# USBC-OVC_LIMIT.net
KiCad netlist of a schematic drawn in EAGLE
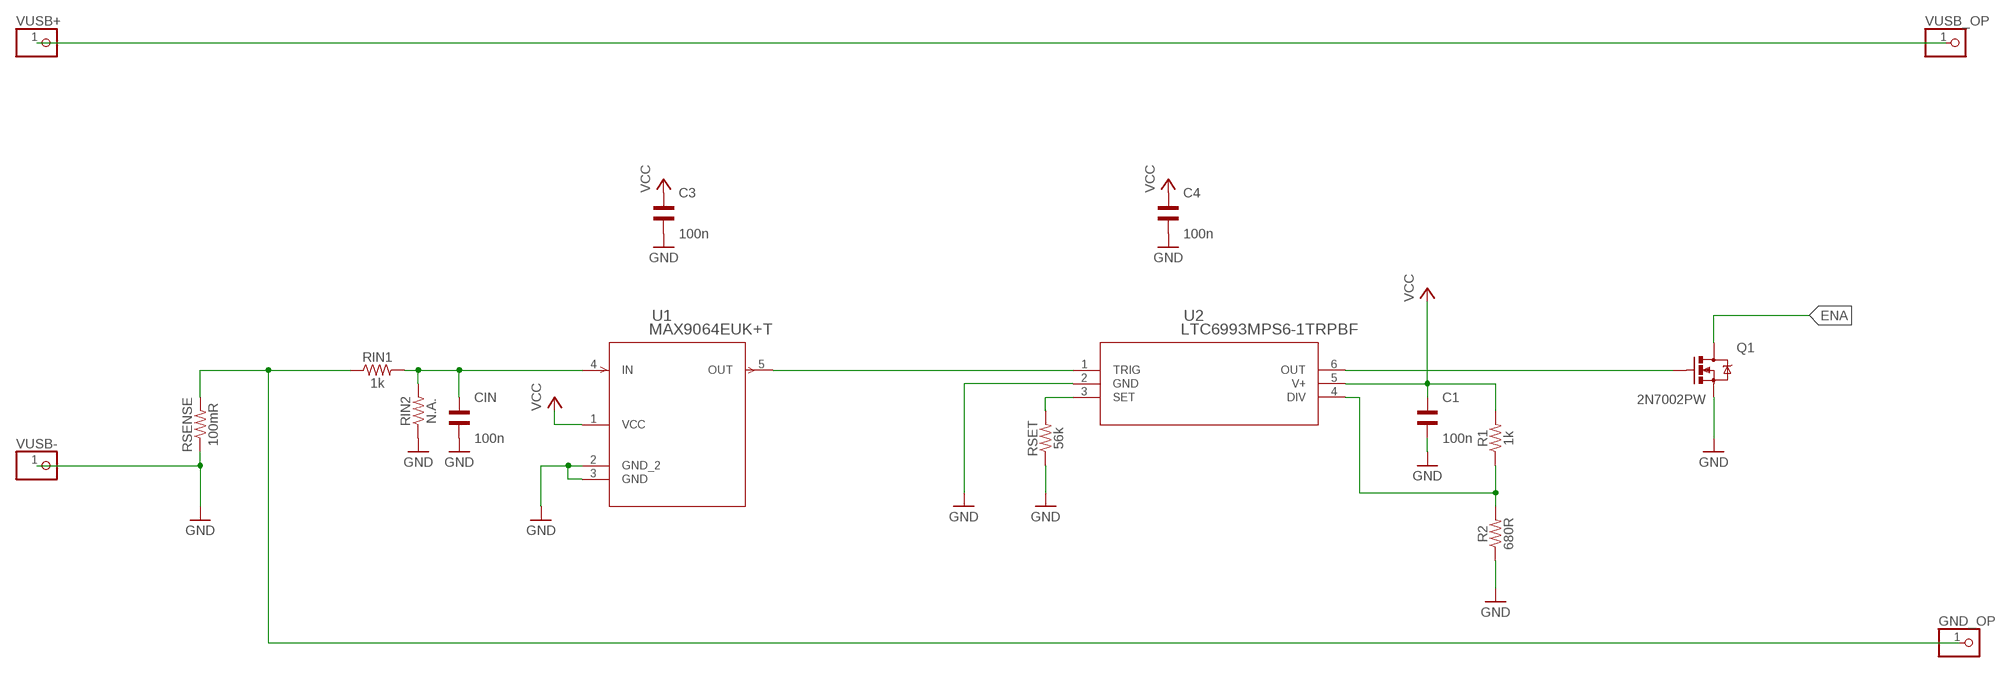
[diagram p0: schematic, sheet 1]

(export (version "E")
  (design (tool "Eeschema 10.0.6"))
  (components
    (comp (ref "C1")
      (value "100n")
      (footprint "eagle-import:WCAP-CSGP_1206")
      (libsource (lib "eagle-import") (part "WCAP-CSGP_1206_885012008001"))
    )
    (comp (ref "C3")
      (value "100n")
      (footprint "eagle-import:WCAP-CSGP_1206")
      (libsource (lib "eagle-import") (part "WCAP-CSGP_1206_885012008001"))
    )
    (comp (ref "C4")
      (value "100n")
      (footprint "eagle-import:WCAP-CSGP_1206")
      (libsource (lib "eagle-import") (part "WCAP-CSGP_1206_885012008001"))
    )
    (comp (ref "CIN")
      (value "100n")
      (footprint "eagle-import:WCAP-CSGP_1206")
      (libsource (lib "eagle-import") (part "WCAP-CSGP_1206_885012008001"))
    )
    (comp (ref "GND_OP")
      (value "PINHD-1X1")
      (footprint "eagle-import:1X01")
      (libsource (lib "eagle-import") (part "PINHD-1X1"))
    )
    (comp (ref "Q1")
      (value "2N7002PW")
      (footprint "eagle-import:SOT323")
      (libsource (lib "eagle-import") (part "MOSFET-NCHANNEL2N7002PW"))
    )
    (comp (ref "R1")
      (value "1k")
      (footprint "eagle-import:1206")
      (libsource (lib "eagle-import") (part "RESISTOR1206"))
    )
    (comp (ref "R2")
      (value "680R")
      (footprint "eagle-import:1206")
      (libsource (lib "eagle-import") (part "RESISTOR1206"))
    )
    (comp (ref "RIN1")
      (value "1k")
      (footprint "eagle-import:1206")
      (libsource (lib "eagle-import") (part "RESISTOR1206"))
    )
    (comp (ref "RIN2")
      (value "N.A.")
      (footprint "eagle-import:1206")
      (libsource (lib "eagle-import") (part "RESISTOR1206"))
    )
    (comp (ref "RSENSE")
      (value "100mR")
      (footprint "eagle-import:1206")
      (libsource (lib "eagle-import") (part "RESISTOR1206"))
    )
    (comp (ref "RSET")
      (value "56k")
      (footprint "eagle-import:1206")
      (libsource (lib "eagle-import") (part "RESISTOR1206"))
    )
    (comp (ref "U1")
      (value "MAX9064EUK+T")
      (footprint "eagle-import:21-0057F_MXM")
      (fields (field (name "COPYRIGHT") "Copyright (C) 2022 Ultra Librarian. All rights reserved."))
      (libsource (lib "eagle-import") (part "MAX9064EUK+T"))
    )
    (comp (ref "U2")
      (value "LTC6993MPS6-1TRPBF")
      (footprint "eagle-import:TSOT-23_S6_LIT")
      (fields
        (field (name "MANUFACTURER_PART_NUMBER") "LTC6993MPS6-1#TRPBF")
        (field (name "COPYRIGHT") "Copyright (C) 2022 Ultra Librarian. All rights reserved.")
      )
      (libsource (lib "eagle-import") (part "LTC6993MPS6-1TRPBF"))
    )
    (comp (ref "VUSB+")
      (value "PINHD-1X1")
      (footprint "eagle-import:1X01")
      (libsource (lib "eagle-import") (part "PINHD-1X1"))
    )
    (comp (ref "VUSB-")
      (value "PINHD-1X1")
      (footprint "eagle-import:1X01")
      (libsource (lib "eagle-import") (part "PINHD-1X1"))
    )
    (comp (ref "VUSB_OP")
      (value "PINHD-1X1")
      (footprint "eagle-import:1X01")
      (libsource (lib "eagle-import") (part "PINHD-1X1"))
    )
  )
  (nets
    (net (code "1") (name "ENA") (class "Default")
      (node (ref "Q1") (pin "3") (pinfunction "D_3") (pintype "passive"))
    )
    (net (code "2") (name "GND") (class "Default")
      (node (ref "C1") (pin "1") (pinfunction "1_1") (pintype "passive"))
      (node (ref "C3") (pin "1") (pinfunction "1_1") (pintype "passive"))
      (node (ref "C4") (pin "1") (pinfunction "1_1") (pintype "passive"))
      (node (ref "CIN") (pin "1") (pinfunction "1_1") (pintype "passive"))
      (node (ref "Q1") (pin "2") (pinfunction "S_2") (pintype "passive"))
      (node (ref "R2") (pin "1") (pinfunction "1_1") (pintype "passive"))
      (node (ref "RIN2") (pin "1") (pinfunction "1_1") (pintype "passive"))
      (node (ref "RSENSE") (pin "1") (pinfunction "1_1") (pintype "passive"))
      (node (ref "RSET") (pin "1") (pinfunction "1_1") (pintype "passive"))
      (node (ref "U1") (pin "2") (pinfunction "GND_2_2") (pintype "power_in"))
      (node (ref "U1") (pin "3") (pinfunction "GND_3") (pintype "power_in"))
      (node (ref "U2") (pin "2") (pinfunction "GND_2") (pintype "power_in"))
      (node (ref "VUSB-") (pin "1") (pinfunction "1_1") (pintype "passive"))
    )
    (net (code "3") (name "Net-(GND_OP-Pad1)") (class "Default")
      (node (ref "GND_OP") (pin "1") (pinfunction "1_1") (pintype "passive"))
      (node (ref "RIN1") (pin "1") (pinfunction "1_1") (pintype "passive"))
      (node (ref "RSENSE") (pin "2") (pinfunction "2_2") (pintype "passive"))
    )
    (net (code "4") (name "Net-(Q1-G)") (class "Default")
      (node (ref "Q1") (pin "1") (pinfunction "G_1") (pintype "passive"))
      (node (ref "U2") (pin "6") (pinfunction "OUT_6") (pintype "output"))
    )
    (net (code "5") (name "Net-(U1-IN)") (class "Default")
      (node (ref "CIN") (pin "2") (pinfunction "2_2") (pintype "passive"))
      (node (ref "RIN1") (pin "2") (pinfunction "2_2") (pintype "passive"))
      (node (ref "RIN2") (pin "2") (pinfunction "2_2") (pintype "passive"))
      (node (ref "U1") (pin "4") (pinfunction "IN_4") (pintype "input"))
    )
    (net (code "6") (name "Net-(U1-OUT)") (class "Default")
      (node (ref "U1") (pin "5") (pinfunction "OUT_5") (pintype "output"))
      (node (ref "U2") (pin "1") (pinfunction "TRIG_1") (pintype "input"))
    )
    (net (code "7") (name "Net-(U2-DIV)") (class "Default")
      (node (ref "R1") (pin "1") (pinfunction "1_1") (pintype "passive"))
      (node (ref "R2") (pin "2") (pinfunction "2_2") (pintype "passive"))
      (node (ref "U2") (pin "4") (pinfunction "DIV_4") (pintype "input"))
    )
    (net (code "8") (name "Net-(U2-SET)") (class "Default")
      (node (ref "RSET") (pin "2") (pinfunction "2_2") (pintype "passive"))
      (node (ref "U2") (pin "3") (pinfunction "SET_3") (pintype "input"))
    )
    (net (code "9") (name "Net-(VUSB+-Pad1)") (class "Default")
      (node (ref "VUSB+") (pin "1") (pinfunction "1_1") (pintype "passive"))
      (node (ref "VUSB_OP") (pin "1") (pinfunction "1_1") (pintype "passive"))
    )
    (net (code "10") (name "VCC") (class "Default")
      (node (ref "C1") (pin "2") (pinfunction "2_2") (pintype "passive"))
      (node (ref "C3") (pin "2") (pinfunction "2_2") (pintype "passive"))
      (node (ref "C4") (pin "2") (pinfunction "2_2") (pintype "passive"))
      (node (ref "R1") (pin "2") (pinfunction "2_2") (pintype "passive"))
      (node (ref "U1") (pin "1") (pinfunction "VCC_1") (pintype "power_in"))
      (node (ref "U2") (pin "5") (pinfunction "V+_5") (pintype "power_in"))
    )
  )
)
